# ProDoc_Schematic_2025-12-04.net
KiCad netlist of a schematic drawn in EasyEDA Pro
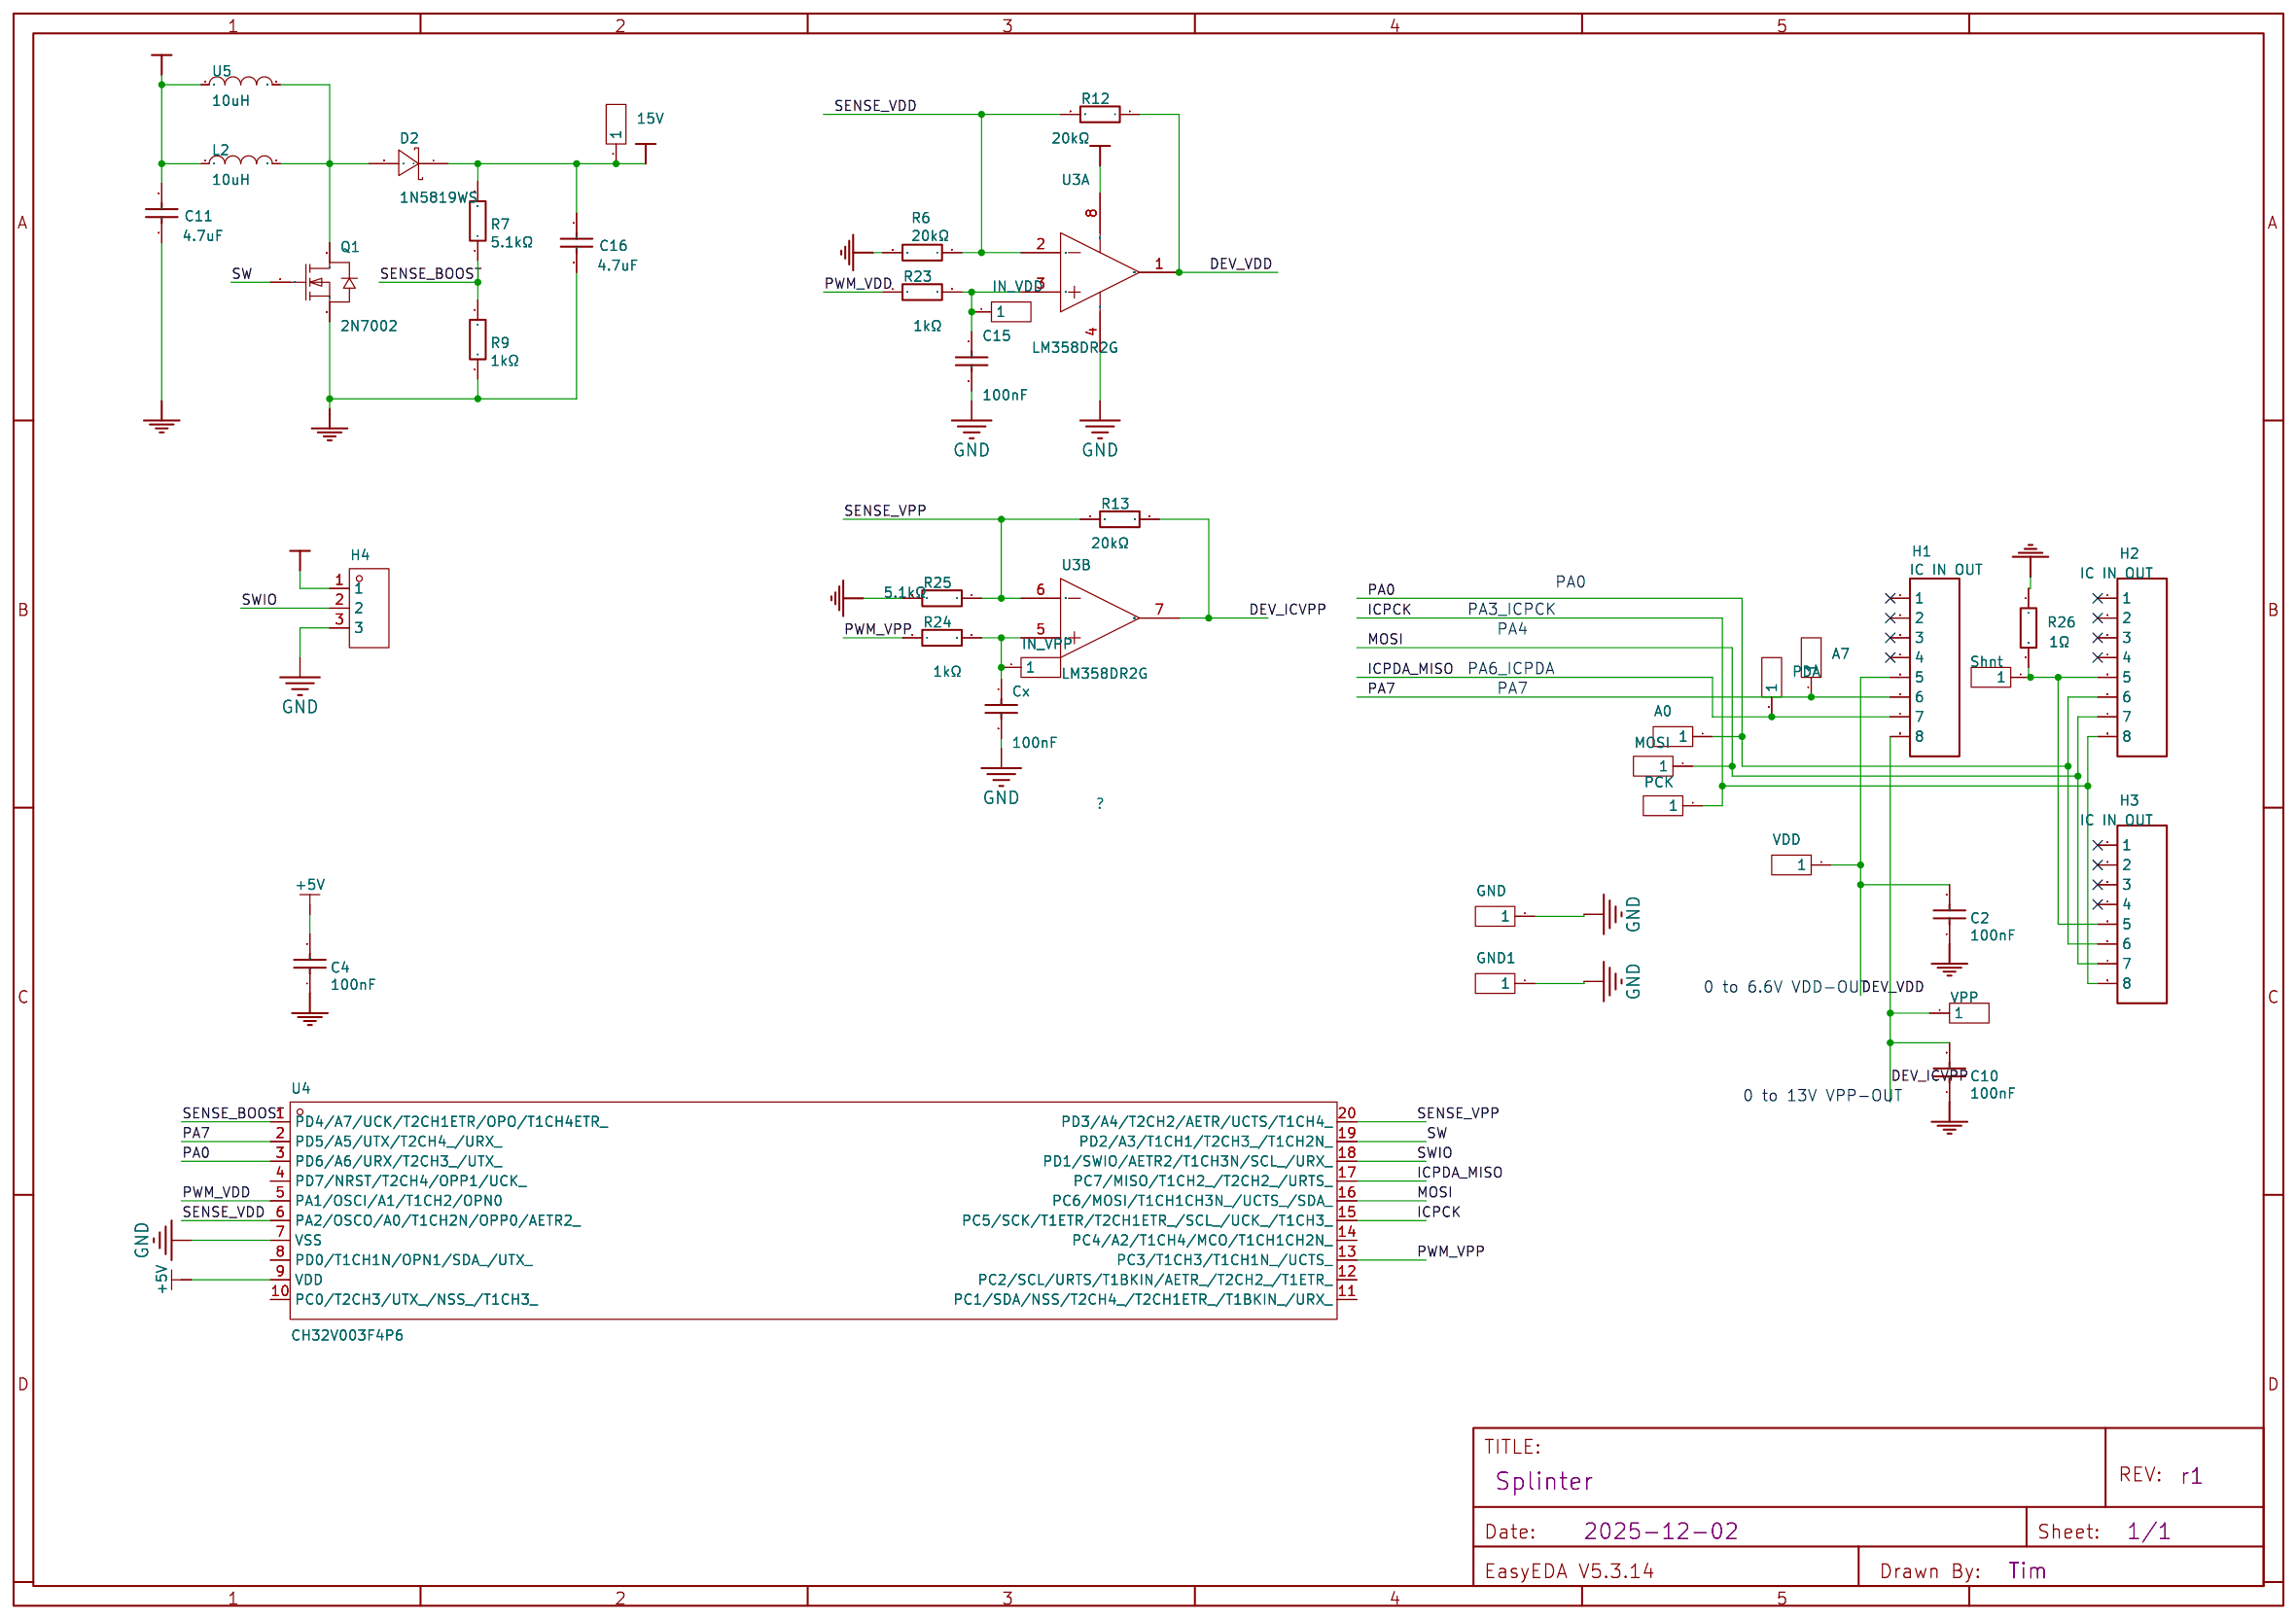
[diagram p0: schematic sheet]

(export (version "E")
  (design (tool "Eeschema 10.0.6"))
  (components
    (comp (ref "15V")
      (value "~")
      (footprint "easyedapro:HDR-TH_1P-V-M_XKB_X4611WV-01I-C28D40")
      (libsource (lib "easyedapro") (part "HDR_1x1"))
    )
    (comp (ref "A0")
      (value "~")
      (footprint "easyedapro:HDR-TH_1P-V-M_XKB_X4611WV-01I-C28D40")
      (libsource (lib "easyedapro") (part "HDR_1x1"))
    )
    (comp (ref "A7")
      (value "~")
      (footprint "easyedapro:HDR-TH_1P-V-M_XKB_X4611WV-01I-C28D40")
      (libsource (lib "easyedapro") (part "HDR_1x1"))
    )
    (comp (ref "C2")
      (value "100nF")
      (description "Capacitance:100nF Tolerance:±10% Tolerance:±10% Voltage Rating:16V Temperature Coefficient:X7R")
      (fields
        (field (name "Manufacturer Part") "CL05B104KO5NNNC")
        (field (name "Manufacturer") "SAMSUNG(三星)")
      )
      (libsource (lib "easyedapro") (part "100nF"))
    )
    (comp (ref "C4")
      (value "100nF")
      (description "Capacitance:100nF Tolerance:±10% Tolerance:±10% Voltage Rating:16V Temperature Coefficient:X7R")
      (fields
        (field (name "Manufacturer Part") "CL05B104KO5NNNC")
        (field (name "Manufacturer") "SAMSUNG(三星)")
      )
      (libsource (lib "easyedapro") (part "100nF"))
    )
    (comp (ref "C10")
      (value "100nF")
      (description "Capacitance:100nF Tolerance:±10% Tolerance:±10% Voltage Rating:16V Temperature Coefficient:X7R")
      (fields
        (field (name "Manufacturer Part") "CL05B104KO5NNNC")
        (field (name "Manufacturer") "SAMSUNG(三星)")
      )
      (libsource (lib "easyedapro") (part "100nF"))
    )
    (comp (ref "C11")
      (value "4.7uF")
      (description "Capacitance:4.7uF Tolerance:±10% Tolerance:±10% Voltage Rating:16V Temperature Coefficient:X5R")
      (fields
        (field (name "Manufacturer Part") "CL10A475KO8NNNC")
        (field (name "Manufacturer") "SAMSUNG(三星)")
      )
      (libsource (lib "easyedapro") (part "4.7uF"))
    )
    (comp (ref "C15")
      (value "100nF")
      (description "Capacitance:100nF Tolerance:±10% Tolerance:±10% Voltage Rating:16V Temperature Coefficient:X7R")
      (fields
        (field (name "Manufacturer Part") "CL05B104KO5NNNC")
        (field (name "Manufacturer") "SAMSUNG(三星)")
      )
      (libsource (lib "easyedapro") (part "100nF"))
    )
    (comp (ref "C16")
      (value "4.7uF")
      (description "Capacitance:4.7uF Tolerance:±10% Tolerance:±10% Voltage Rating:16V Temperature Coefficient:X5R")
      (fields
        (field (name "Manufacturer Part") "CL10A475KO8NNNC")
        (field (name "Manufacturer") "SAMSUNG(三星)")
      )
      (libsource (lib "easyedapro") (part "4.7uF"))
    )
    (comp (ref "Cx")
      (value "100nF")
      (description "Capacitance:100nF Tolerance:±10% Tolerance:±10% Voltage Rating:16V Temperature Coefficient:X7R")
      (fields
        (field (name "Manufacturer Part") "CL05B104KO5NNNC")
        (field (name "Manufacturer") "SAMSUNG(三星)")
      )
      (libsource (lib "easyedapro") (part "100nF"))
    )
    (comp (ref "D2")
      (value "1N5819WS")
      (footprint "easyedapro:SOD-323_L1.8-W1.3-LS2.5-RD")
      (fields (field (name "Manufacturer") "Hottech(合科泰)"))
      (libsource (lib "easyedapro") (part "1N5819WS"))
    )
    (comp (ref "GND")
      (value "~")
      (footprint "easyedapro:HDR-TH_1P-V-M_XKB_X4611WV-01I-C28D40")
      (libsource (lib "easyedapro") (part "HDR_1x1"))
    )
    (comp (ref "GND1")
      (value "~")
      (footprint "easyedapro:HDR-TH_1P-V-M_XKB_X4611WV-01I-C28D40")
      (libsource (lib "easyedapro") (part "HDR_1x1"))
    )
    (comp (ref "H1")
      (value "IC IN OUT")
      (footprint "easyedapro:210S-1X8P")
      (fields
        (field (name "Manufacturer Part") "210S-1*8P L=11.6MMGold-plated black")
        (field (name "Manufacturer") "Ckmtw")
        (field (name "Contributor") "LCSC")
      )
      (libsource (lib "easyedapro") (part "IC IN OUT"))
    )
    (comp (ref "H2")
      (value "IC IN OUT")
      (footprint "easyedapro:210S-1X8P")
      (fields
        (field (name "Manufacturer Part") "210S-1*8P L=11.6MMGold-plated black")
        (field (name "Manufacturer") "Ckmtw")
        (field (name "Contributor") "LCSC")
      )
      (libsource (lib "easyedapro") (part "IC IN OUT"))
    )
    (comp (ref "H3")
      (value "IC IN OUT")
      (footprint "easyedapro:210S-1X8P")
      (fields
        (field (name "Manufacturer Part") "210S-1*8P L=11.6MMGold-plated black")
        (field (name "Manufacturer") "Ckmtw")
        (field (name "Contributor") "LCSC")
      )
      (libsource (lib "easyedapro") (part "IC IN OUT"))
    )
    (comp (ref "H4")
      (value "~")
      (footprint "easyedapro:HDR-TH_3P-P2.54-V-F")
      (libsource (lib "easyedapro") (part "PM254V-11-03-H85"))
    )
    (comp (ref "IN_VDD")
      (value "~")
      (footprint "easyedapro:HDR-TH_1P-V-M_XKB_X4611WV-01I-C28D40")
      (libsource (lib "easyedapro") (part "HDR_1x1"))
    )
    (comp (ref "IN_VPP")
      (value "~")
      (footprint "easyedapro:HDR-TH_1P-V-M_XKB_X4611WV-01I-C28D40")
      (libsource (lib "easyedapro") (part "HDR_1x1"))
    )
    (comp (ref "L2")
      (value "10uH")
      (footprint "easyedapro:L0805")
      (description "Inductance:10uH Tolerance:±20% Tolerance:±20% Current Rating:400mA DC Resistance(DCR):-")
      (fields
        (field (name "Manufacturer Part") "CPY201212T-100M-NP")
        (field (name "Manufacturer") "Chilisin(奇力新)")
      )
      (libsource (lib "easyedapro") (part "CPY201212T-100M-NP"))
    )
    (comp (ref "MOSI")
      (value "~")
      (footprint "easyedapro:HDR-TH_1P-V-M_XKB_X4611WV-01I-C28D40")
      (libsource (lib "easyedapro") (part "HDR_1x1"))
    )
    (comp (ref "PCK")
      (value "~")
      (footprint "easyedapro:HDR-TH_1P-V-M_XKB_X4611WV-01I-C28D40")
      (libsource (lib "easyedapro") (part "HDR_1x1"))
    )
    (comp (ref "PDA")
      (value "~")
      (footprint "easyedapro:HDR-TH_1P-V-M_XKB_X4611WV-01I-C28D40")
      (libsource (lib "easyedapro") (part "HDR_1x1"))
    )
    (comp (ref "Q1")
      (value "2N7002")
      (footprint "easyedapro:SOT-23-3_L2.9-W1.3-P1.90-LS2.4-BR")
      (fields (field (name "Manufacturer") "CJ(江苏长电/长晶)"))
      (libsource (lib "easyedapro") (part "2N7002"))
    )
    (comp (ref "R6")
      (value "20kΩ")
      (fields
        (field (name "Manufacturer Part") "0402WGF2002TCE")
        (field (name "Manufacturer") "UNI-ROYAL(厚声)")
      )
      (libsource (lib "") (part "20K_1"))
    )
    (comp (ref "R7")
      (value "5.1kΩ")
      (fields
        (field (name "Manufacturer Part") "0402WGF5101TCE")
        (field (name "Manufacturer") "UNI-ROYAL(厚声)")
      )
      (libsource (lib "easyedapro") (part "100K"))
    )
    (comp (ref "R9")
      (value "1kΩ")
      (fields
        (field (name "Manufacturer Part") "0402WGF1001TCE")
        (field (name "Manufacturer") "UNI-ROYAL(厚声)")
      )
      (libsource (lib "easyedapro") (part "3.9K"))
    )
    (comp (ref "R12")
      (value "20kΩ")
      (fields
        (field (name "Manufacturer Part") "0402WGF2002TCE")
        (field (name "Manufacturer") "UNI-ROYAL(厚声)")
      )
      (libsource (lib "easyedapro") (part "20K"))
    )
    (comp (ref "R13")
      (value "20kΩ")
      (fields
        (field (name "Manufacturer Part") "0402WGF2002TCE")
        (field (name "Manufacturer") "UNI-ROYAL(厚声)")
      )
      (libsource (lib "easyedapro") (part "20K"))
    )
    (comp (ref "R23")
      (value "1kΩ")
      (fields
        (field (name "Manufacturer Part") "0402WGF1001TCE")
        (field (name "Manufacturer") "UNI-ROYAL(厚声)")
      )
      (libsource (lib "easyedapro") (part "3.9K"))
    )
    (comp (ref "R24")
      (value "1kΩ")
      (fields
        (field (name "Manufacturer Part") "0402WGF1001TCE")
        (field (name "Manufacturer") "UNI-ROYAL(厚声)")
      )
      (libsource (lib "easyedapro") (part "3.9K"))
    )
    (comp (ref "R25")
      (value "5.1kΩ")
      (fields
        (field (name "Manufacturer Part") "0402WGF5101TCE")
        (field (name "Manufacturer") "UNI-ROYAL(厚声)")
      )
      (libsource (lib "easyedapro") (part "20K"))
    )
    (comp (ref "R26")
      (value "1Ω")
      (fields
        (field (name "Manufacturer Part") "0603WAF100KT5E")
        (field (name "Manufacturer") "UNI-ROYAL(厚声)")
      )
      (libsource (lib "easyedapro") (part "20K"))
    )
    (comp (ref "Shnt")
      (value "~")
      (footprint "easyedapro:HDR-TH_1P-V-M_XKB_X4611WV-01I-C28D40")
      (libsource (lib "easyedapro") (part "HDR_1x1"))
    )
    (comp (ref "U3")
      (value "LM358DR2G")
      (fields (field (name "Manufacturer") "onsemi(安森美)"))
      (libsource (lib "easyedapro") (part "LM358_C18164495"))
    )
    (comp (ref "U4")
      (value "CH32V003F4P6")
      (footprint "easyedapro:TSSOP-20_L6.5-W4.4-P0.65-LS6.4-BL")
      (fields (field (name "Manufacturer") "WCH(南京沁恒)"))
      (libsource (lib "easyedapro") (part "CH32V003F4P6"))
    )
    (comp (ref "U5")
      (value "10uH")
      (footprint "easyedapro:IND-TH_BD3.0-L7.6-P11.60-D0.5")
      (fields
        (field (name "Manufacturer Part") "AL0307-100K")
        (field (name "Manufacturer") "LanTu Micro(蓝图微电)")
      )
      (libsource (lib "easyedapro") (part "AL0307-100K_C19704343"))
    )
    (comp (ref "VDD")
      (value "~")
      (footprint "easyedapro:HDR-TH_1P-V-M_XKB_X4611WV-01I-C28D40")
      (libsource (lib "easyedapro") (part "HDR_1x1"))
    )
    (comp (ref "VPP")
      (value "~")
      (footprint "easyedapro:HDR-TH_1P-V-M_XKB_X4611WV-01I-C28D40")
      (libsource (lib "easyedapro") (part "HDR_1x1"))
    )
  )
  (nets
    (net (code "1") (name "+5V") (class "Default")
      (node (ref "C11") (pin "1") (pinfunction "1_1") (pintype "input"))
      (node (ref "C4") (pin "2") (pinfunction "2_2") (pintype "input"))
      (node (ref "H4") (pin "1") (pinfunction "1_1") (pintype "unspecified"))
      (node (ref "L2") (pin "1") (pinfunction "1_1") (pintype "unspecified"))
      (node (ref "U4") (pin "9") (pinfunction "VDD_9") (pintype "unspecified"))
      (node (ref "U5") (pin "1") (pinfunction "1_1") (pintype "unspecified"))
    )
    (net (code "2") (name "/DEV_ICVPP") (class "Default")
      (node (ref "C10") (pin "2") (pinfunction "2_2") (pintype "input"))
      (node (ref "H1") (pin "8") (pinfunction "8_8") (pintype "unspecified"))
      (node (ref "R13") (pin "1") (pinfunction "1_1") (pintype "input"))
      (node (ref "U3") (pin "7") (pinfunction "OUT_B_7") (pintype "output"))
      (node (ref "VPP") (pin "1") (pinfunction "1_1") (pintype "unspecified"))
    )
    (net (code "3") (name "/DEV_VDD") (class "Default")
      (node (ref "C2") (pin "2") (pinfunction "2_2") (pintype "input"))
      (node (ref "H1") (pin "5") (pinfunction "5_5") (pintype "unspecified"))
      (node (ref "R12") (pin "1") (pinfunction "1_1") (pintype "input"))
      (node (ref "U3") (pin "1") (pinfunction "OUT_A_1") (pintype "output"))
      (node (ref "VDD") (pin "1") (pinfunction "1_1") (pintype "unspecified"))
    )
    (net (code "4") (name "/ICPCK") (class "Default")
      (node (ref "H2") (pin "8") (pinfunction "8_8") (pintype "unspecified"))
      (node (ref "H3") (pin "8") (pinfunction "8_8") (pintype "unspecified"))
      (node (ref "PCK") (pin "1") (pinfunction "1_1") (pintype "unspecified"))
      (node (ref "U4") (pin "15") (pinfunction "PC5/SCK/T1ETR/T2CH1ETR_/SCL_/UCK_/T1CH3__15") (pintype "unspecified"))
    )
    (net (code "5") (name "/ICPDA_MISO") (class "Default")
      (node (ref "H1") (pin "7") (pinfunction "7_7") (pintype "unspecified"))
      (node (ref "PDA") (pin "1") (pinfunction "1_1") (pintype "unspecified"))
      (node (ref "U4") (pin "17") (pinfunction "PC7/MISO/T1CH2_/T2CH2_/URTS__17") (pintype "unspecified"))
    )
    (net (code "6") (name "/MOSI") (class "Default")
      (node (ref "H2") (pin "7") (pinfunction "7_7") (pintype "unspecified"))
      (node (ref "H3") (pin "7") (pinfunction "7_7") (pintype "unspecified"))
      (node (ref "MOSI") (pin "1") (pinfunction "1_1") (pintype "unspecified"))
      (node (ref "U4") (pin "16") (pinfunction "PC6/MOSI/T1CH1CH3N_/UCTS_/SDA__16") (pintype "unspecified"))
    )
    (net (code "7") (name "/PA0") (class "Default")
      (node (ref "A0") (pin "1") (pinfunction "1_1") (pintype "unspecified"))
      (node (ref "H2") (pin "6") (pinfunction "6_6") (pintype "unspecified"))
      (node (ref "H3") (pin "6") (pinfunction "6_6") (pintype "unspecified"))
      (node (ref "U4") (pin "3") (pinfunction "PD6/A6/URX/T2CH3_/UTX__3") (pintype "unspecified"))
    )
    (net (code "8") (name "/PA7") (class "Default")
      (node (ref "A7") (pin "1") (pinfunction "1_1") (pintype "unspecified"))
      (node (ref "H1") (pin "6") (pinfunction "6_6") (pintype "unspecified"))
      (node (ref "U4") (pin "2") (pinfunction "PD5/A5/UTX/T2CH4_/URX__2") (pintype "unspecified"))
    )
    (net (code "9") (name "/PWM_VDD") (class "Default")
      (node (ref "R23") (pin "1") (pinfunction "1_1") (pintype "input"))
      (node (ref "U4") (pin "5") (pinfunction "PA1/OSCI/A1/T1CH2/OPN0_5") (pintype "unspecified"))
    )
    (net (code "10") (name "/PWM_VPP") (class "Default")
      (node (ref "R24") (pin "1") (pinfunction "1_1") (pintype "input"))
      (node (ref "U4") (pin "13") (pinfunction "PC3/T1CH3/T1CH1N_/UCTS__13") (pintype "unspecified"))
    )
    (net (code "11") (name "/SENSE_BOOST") (class "Default")
      (node (ref "R7") (pin "1") (pinfunction "1_1") (pintype "input"))
      (node (ref "R9") (pin "1") (pinfunction "1_1") (pintype "input"))
      (node (ref "U4") (pin "1") (pinfunction "PD4/A7/UCK/T2CH1ETR/OPO/T1CH4ETR__1") (pintype "unspecified"))
    )
    (net (code "12") (name "/SENSE_VDD") (class "Default")
      (node (ref "R12") (pin "2") (pinfunction "2_2") (pintype "input"))
      (node (ref "R6") (pin "1") (pinfunction "1_1") (pintype "input"))
      (node (ref "U3") (pin "2") (pinfunction "IN_A-_2") (pintype "unspecified"))
      (node (ref "U4") (pin "6") (pinfunction "PA2/OSCO/A0/T1CH2N/OPP0/AETR2__6") (pintype "unspecified"))
    )
    (net (code "13") (name "/SENSE_VPP") (class "Default")
      (node (ref "R13") (pin "2") (pinfunction "2_2") (pintype "input"))
      (node (ref "R25") (pin "1") (pinfunction "1_1") (pintype "input"))
      (node (ref "U3") (pin "6") (pinfunction "IN_B-_6") (pintype "unspecified"))
      (node (ref "U4") (pin "20") (pinfunction "PD3/A4/T2CH2/AETR/UCTS/T1CH4__20") (pintype "unspecified"))
    )
    (net (code "14") (name "/SW") (class "Default")
      (node (ref "Q1") (pin "1") (pinfunction "G_1") (pintype "unspecified"))
      (node (ref "U4") (pin "19") (pinfunction "PD2/A3/T1CH1/T2CH3_/T1CH2N__19") (pintype "unspecified"))
    )
    (net (code "15") (name "/SWIO") (class "Default")
      (node (ref "H4") (pin "2") (pinfunction "2_2") (pintype "unspecified"))
      (node (ref "U4") (pin "18") (pinfunction "PD1/SWIO/AETR2/T1CH3N/SCL_/URX__18") (pintype "unspecified"))
    )
    (net (code "16") (name "15V") (class "Default")
      (node (ref "15V") (pin "1") (pinfunction "1_1") (pintype "unspecified"))
      (node (ref "C16") (pin "1") (pinfunction "1_1") (pintype "input"))
      (node (ref "D2") (pin "1") (pinfunction "K_1") (pintype "unspecified"))
      (node (ref "R7") (pin "2") (pinfunction "2_2") (pintype "input"))
      (node (ref "U3") (pin "8") (pinfunction "VCC_8") (pintype "unspecified"))
    )
    (net (code "17") (name "GND") (class "Default")
      (node (ref "C10") (pin "1") (pinfunction "1_1") (pintype "input"))
      (node (ref "C11") (pin "2") (pinfunction "2_2") (pintype "input"))
      (node (ref "C15") (pin "2") (pinfunction "2_2") (pintype "input"))
      (node (ref "C16") (pin "2") (pinfunction "2_2") (pintype "input"))
      (node (ref "C2") (pin "1") (pinfunction "1_1") (pintype "input"))
      (node (ref "C4") (pin "1") (pinfunction "1_1") (pintype "input"))
      (node (ref "Cx") (pin "2") (pinfunction "2_2") (pintype "input"))
      (node (ref "GND") (pin "1") (pinfunction "1_1") (pintype "unspecified"))
      (node (ref "GND1") (pin "1") (pinfunction "1_1") (pintype "unspecified"))
      (node (ref "H4") (pin "3") (pinfunction "3_3") (pintype "unspecified"))
      (node (ref "Q1") (pin "2") (pinfunction "S_2") (pintype "unspecified"))
      (node (ref "R25") (pin "2") (pinfunction "2_2") (pintype "input"))
      (node (ref "R26") (pin "1") (pinfunction "1_1") (pintype "input"))
      (node (ref "R6") (pin "2") (pinfunction "2_2") (pintype "input"))
      (node (ref "R9") (pin "2") (pinfunction "2_2") (pintype "input"))
      (node (ref "U3") (pin "4") (pinfunction "VEE_4") (pintype "unspecified"))
      (node (ref "U4") (pin "7") (pinfunction "VSS_7") (pintype "unspecified"))
    )
    (net (code "18") (name "Net-(D2-A)") (class "Default")
      (node (ref "D2") (pin "2") (pinfunction "A_2") (pintype "unspecified"))
      (node (ref "L2") (pin "2") (pinfunction "2_2") (pintype "unspecified"))
      (node (ref "Q1") (pin "3") (pinfunction "D_3") (pintype "unspecified"))
      (node (ref "U5") (pin "2") (pinfunction "2_2") (pintype "unspecified"))
    )
    (net (code "19") (name "Net-(H2-Pad5)") (class "Default")
      (node (ref "H2") (pin "5") (pinfunction "5_5") (pintype "unspecified"))
      (node (ref "H3") (pin "5") (pinfunction "5_5") (pintype "unspecified"))
      (node (ref "R26") (pin "2") (pinfunction "2_2") (pintype "input"))
      (node (ref "Shnt") (pin "1") (pinfunction "1_1") (pintype "unspecified"))
    )
    (net (code "20") (name "Net-(U3A-IN_A+)") (class "Default")
      (node (ref "C15") (pin "1") (pinfunction "1_1") (pintype "input"))
      (node (ref "IN_VDD") (pin "1") (pinfunction "1_1") (pintype "unspecified"))
      (node (ref "R23") (pin "2") (pinfunction "2_2") (pintype "input"))
      (node (ref "U3") (pin "3") (pinfunction "IN_A+_3") (pintype "unspecified"))
    )
    (net (code "21") (name "Net-(U3B-IN_B+)") (class "Default")
      (node (ref "Cx") (pin "1") (pinfunction "1_1") (pintype "input"))
      (node (ref "IN_VPP") (pin "1") (pinfunction "1_1") (pintype "unspecified"))
      (node (ref "R24") (pin "2") (pinfunction "2_2") (pintype "input"))
      (node (ref "U3") (pin "5") (pinfunction "IN_B+_5") (pintype "unspecified"))
    )
    (net (code "22") (name "unconnected-(H1-Pad1)") (class "Default")
      (node (ref "H1") (pin "1") (pinfunction "1_1") (pintype "unspecified+no_connect"))
    )
    (net (code "23") (name "unconnected-(H1-Pad2)") (class "Default")
      (node (ref "H1") (pin "2") (pinfunction "2_2") (pintype "unspecified+no_connect"))
    )
    (net (code "24") (name "unconnected-(H1-Pad3)") (class "Default")
      (node (ref "H1") (pin "3") (pinfunction "3_3") (pintype "unspecified+no_connect"))
    )
    (net (code "25") (name "unconnected-(H1-Pad4)") (class "Default")
      (node (ref "H1") (pin "4") (pinfunction "4_4") (pintype "unspecified+no_connect"))
    )
    (net (code "26") (name "unconnected-(H2-Pad1)") (class "Default")
      (node (ref "H2") (pin "1") (pinfunction "1_1") (pintype "unspecified+no_connect"))
    )
    (net (code "27") (name "unconnected-(H2-Pad2)") (class "Default")
      (node (ref "H2") (pin "2") (pinfunction "2_2") (pintype "unspecified+no_connect"))
    )
    (net (code "28") (name "unconnected-(H2-Pad3)") (class "Default")
      (node (ref "H2") (pin "3") (pinfunction "3_3") (pintype "unspecified+no_connect"))
    )
    (net (code "29") (name "unconnected-(H2-Pad4)") (class "Default")
      (node (ref "H2") (pin "4") (pinfunction "4_4") (pintype "unspecified+no_connect"))
    )
    (net (code "30") (name "unconnected-(H3-Pad1)") (class "Default")
      (node (ref "H3") (pin "1") (pinfunction "1_1") (pintype "unspecified+no_connect"))
    )
    (net (code "31") (name "unconnected-(H3-Pad2)") (class "Default")
      (node (ref "H3") (pin "2") (pinfunction "2_2") (pintype "unspecified+no_connect"))
    )
    (net (code "32") (name "unconnected-(H3-Pad3)") (class "Default")
      (node (ref "H3") (pin "3") (pinfunction "3_3") (pintype "unspecified+no_connect"))
    )
    (net (code "33") (name "unconnected-(H3-Pad4)") (class "Default")
      (node (ref "H3") (pin "4") (pinfunction "4_4") (pintype "unspecified+no_connect"))
    )
    (net (code "34") (name "unconnected-(U4-PC0{slash}T2CH3{slash}UTX_{slash}NSS_{slash}T1CH3_-Pad10)") (class "Default")
      (node (ref "U4") (pin "10") (pinfunction "PC0/T2CH3/UTX_/NSS_/T1CH3__10") (pintype "unspecified"))
    )
    (net (code "35") (name "unconnected-(U4-PC1{slash}SDA{slash}NSS{slash}T2CH4_{slash}T2CH1ETR_{slash}T1BKIN_{slash}URX_-Pad11)") (class "Default")
      (node (ref "U4") (pin "11") (pinfunction "PC1/SDA/NSS/T2CH4_/T2CH1ETR_/T1BKIN_/URX__11") (pintype "unspecified"))
    )
    (net (code "36") (name "unconnected-(U4-PC2{slash}SCL{slash}URTS{slash}T1BKIN{slash}AETR_{slash}T2CH2_{slash}T1ETR_-Pad12)") (class "Default")
      (node (ref "U4") (pin "12") (pinfunction "PC2/SCL/URTS/T1BKIN/AETR_/T2CH2_/T1ETR__12") (pintype "unspecified"))
    )
    (net (code "37") (name "unconnected-(U4-PC4{slash}A2{slash}T1CH4{slash}MCO{slash}T1CH1CH2N_-Pad14)") (class "Default")
      (node (ref "U4") (pin "14") (pinfunction "PC4/A2/T1CH4/MCO/T1CH1CH2N__14") (pintype "unspecified"))
    )
    (net (code "38") (name "unconnected-(U4-PD0{slash}T1CH1N{slash}OPN1{slash}SDA_{slash}UTX_-Pad8)") (class "Default")
      (node (ref "U4") (pin "8") (pinfunction "PD0/T1CH1N/OPN1/SDA_/UTX__8") (pintype "unspecified"))
    )
    (net (code "39") (name "unconnected-(U4-PD7{slash}NRST{slash}T2CH4{slash}OPP1{slash}UCK_-Pad4)") (class "Default")
      (node (ref "U4") (pin "4") (pinfunction "PD7/NRST/T2CH4/OPP1/UCK__4") (pintype "unspecified"))
    )
  )
)
